# ZXLD1350.net
KiCad netlist of a schematic drawn in EAGLE
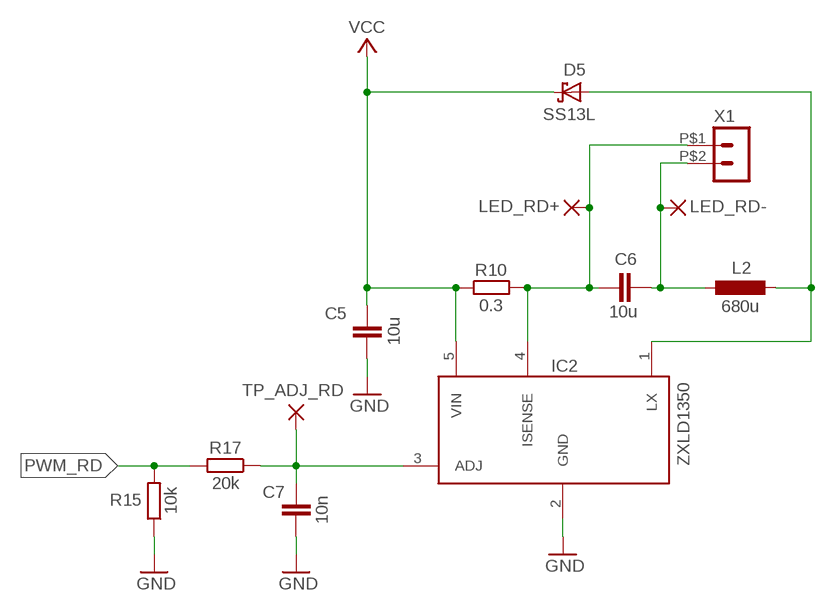
[diagram p0: schematic, sheet 1]

(export (version "E")
  (design (tool "Eeschema 10.0.6"))
  (components
    (comp (ref "C5")
      (value "10u")
      (footprint "eagle-import:C0805K")
      (libsource (lib "eagle-import") (part "C-EUC0805K"))
    )
    (comp (ref "C6")
      (value "10u")
      (footprint "eagle-import:C0805K")
      (libsource (lib "eagle-import") (part "C-EUC0805K"))
    )
    (comp (ref "C7")
      (value "10n")
      (footprint "eagle-import:C0805K")
      (libsource (lib "eagle-import") (part "C-EUC0805K"))
    )
    (comp (ref "D5")
      (value "SS13L")
      (footprint "eagle-import:SUB-SMA")
      (libsource (lib "eagle-import") (part "SS13L"))
    )
    (comp (ref "IC2")
      (value "ZXLD1350")
      (footprint "eagle-import:TSOT23-5L")
      (libsource (lib "eagle-import") (part "ZXLD1350"))
    )
    (comp (ref "L2")
      (value "680u")
      (footprint "eagle-import:POWER-CHOKE_WE-PD")
      (libsource (lib "eagle-import") (part "POWER-CHOKE_WE-PD"))
    )
    (comp (ref "LED_RD+")
      (value "TESTPOINT")
      (footprint "eagle-import:3,2_1,6")
      (libsource (lib "eagle-import") (part "TESTPOINT"))
    )
    (comp (ref "LED_RD-")
      (value "TESTPOINT")
      (footprint "eagle-import:3,2_1,6")
      (libsource (lib "eagle-import") (part "TESTPOINT"))
    )
    (comp (ref "R10")
      (value "0.3")
      (footprint "eagle-import:R1206")
      (libsource (lib "eagle-import") (part "R-EU_R1206"))
    )
    (comp (ref "R15")
      (value "10k")
      (footprint "eagle-import:R0805")
      (libsource (lib "eagle-import") (part "R-EU_R0805"))
    )
    (comp (ref "R17")
      (value "20k")
      (footprint "eagle-import:R0805")
      (libsource (lib "eagle-import") (part "R-EU_R0805"))
    )
    (comp (ref "TP_ADJ_RD")
      (value "TESTPOINT")
      (footprint "eagle-import:3,2_1,6")
      (libsource (lib "eagle-import") (part "TESTPOINT"))
    )
    (comp (ref "X1")
      (value "HEADER_POS2_43650-0215")
      (footprint "eagle-import:43650-0215")
      (libsource (lib "eagle-import") (part "HEADER_POS2_?43650-0215"))
    )
  )
  (nets
    (net (code "1") (name "GND") (class "Default")
      (node (ref "C5") (pin "2") (pinfunction "2_2") (pintype "passive"))
      (node (ref "C7") (pin "2") (pinfunction "2_2") (pintype "passive"))
      (node (ref "IC2") (pin "2") (pinfunction "GND_2") (pintype "bidirectional"))
      (node (ref "R15") (pin "1") (pinfunction "1_1") (pintype "passive"))
    )
    (net (code "2") (name "Net-(IC2-ADJ)") (class "Default")
      (node (ref "C7") (pin "1") (pinfunction "1_1") (pintype "passive"))
      (node (ref "IC2") (pin "3") (pinfunction "ADJ_3") (pintype "bidirectional"))
      (node (ref "R17") (pin "1") (pinfunction "1_1") (pintype "passive"))
      (node (ref "TP_ADJ_RD") (pin "1") (pinfunction "P_1") (pintype "passive"))
    )
    (net (code "3") (name "Net-(IC2-ISENSE)") (class "Default")
      (node (ref "C6") (pin "1") (pinfunction "1_1") (pintype "passive"))
      (node (ref "IC2") (pin "4") (pinfunction "ISENSE_4") (pintype "bidirectional"))
      (node (ref "LED_RD+") (pin "1") (pinfunction "P_1") (pintype "passive"))
      (node (ref "R10") (pin "2") (pinfunction "2_2") (pintype "passive"))
      (node (ref "X1") (pin "P$1") (pinfunction "1_P$1") (pintype "passive"))
    )
    (net (code "4") (name "Net-(IC2-LX)") (class "Default")
      (node (ref "D5") (pin "A") (pinfunction "A_A") (pintype "passive"))
      (node (ref "IC2") (pin "1") (pinfunction "LX_1") (pintype "bidirectional"))
      (node (ref "L2") (pin "2") (pinfunction "2_2") (pintype "passive"))
    )
    (net (code "5") (name "Net-(LED_RD--P)") (class "Default")
      (node (ref "C6") (pin "2") (pinfunction "2_2") (pintype "passive"))
      (node (ref "L2") (pin "1") (pinfunction "1_1") (pintype "passive"))
      (node (ref "LED_RD-") (pin "1") (pinfunction "P_1") (pintype "passive"))
      (node (ref "X1") (pin "P$2") (pinfunction "2_P$2") (pintype "passive"))
    )
    (net (code "6") (name "PWM_RD") (class "Default")
      (node (ref "R15") (pin "2") (pinfunction "2_2") (pintype "passive"))
      (node (ref "R17") (pin "2") (pinfunction "2_2") (pintype "passive"))
    )
    (net (code "7") (name "VCC") (class "Default")
      (node (ref "C5") (pin "1") (pinfunction "1_1") (pintype "passive"))
      (node (ref "D5") (pin "C") (pinfunction "C_C") (pintype "passive"))
      (node (ref "IC2") (pin "5") (pinfunction "VIN_5") (pintype "bidirectional"))
      (node (ref "R10") (pin "1") (pinfunction "1_1") (pintype "passive"))
    )
  )
)
